# Relay.net
KiCad netlist of a schematic drawn in Altium Designer
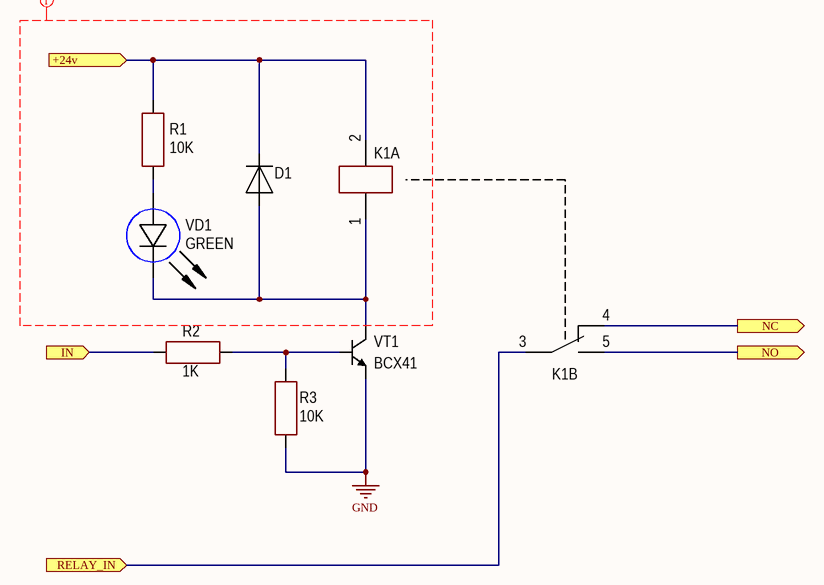
[diagram p0: Relay.SchDoc]

(export (version "E")
  (design (tool "Eeschema 10.0.6"))
  (components
    (comp (ref "D1")
      (value "~")
      (footprint "StandardCase:DIODE: SMA")
      (fields
        (field (name "MANUFACTURER") "Micro Commercial")
        (field (name "VALUEMANUFACTURERPARTNUMBER") "RS1M, SMA")
        (field (name "VOLTAGE") "1000V")
      )
      (libsource (lib "Diode") (part "Diode_single"))
    )
    (comp (ref "K1")
      (value "~")
      (footprint "PcbLib1:REL: TRJ")
      (fields
        (field (name "MANUFACTURER") "Ningbo Songle")
        (field (name "VALUEMANUFACTURERPARTNUMBER") "Electromechanics relay, 3VDC, 250VAC, 10A, 1NO, -40...+85°C")
        (field (name "PARTNUMBER") "TRJ-24VDC-SA-CD-R")
      )
      (libsource (lib "") (part "Relay_NT73_1"))
    )
    (comp (ref "R1")
      (value "10K")
      (footprint "StandardCase:RES: 1206")
      (fields
        (field (name "MANUFACTURER") "Yageo")
        (field (name "PARTNUMBER") "RC1206JR-07100RL")
        (field (name "VALUEMANUFACTURERPARTNUMBER") "Resistor film, 10K, ±5%, 1206, 0.25W, -55...+125°C")
      )
      (libsource (lib "") (part "Resistor_1206_1"))
    )
    (comp (ref "R2")
      (value "1K")
      (footprint "StandardCase:RES: 1206")
      (fields
        (field (name "MANUFACTURER") "Yageo")
        (field (name "PARTNUMBER") "RC1206JR-07100RL")
        (field (name "VALUEMANUFACTURERPARTNUMBER") "Resistor film, 1K, ±5%, 1206, 0.25W, -55...+125°C")
      )
      (libsource (lib "Resistor") (part "Resistor_1206"))
    )
    (comp (ref "R3")
      (value "10K")
      (footprint "StandardCase:RES: 1206")
      (fields
        (field (name "MANUFACTURER") "Yageo")
        (field (name "PARTNUMBER") "RC1206JR-07100RL")
        (field (name "VALUEMANUFACTURERPARTNUMBER") "Resistor film, 10K, ±5%, 1206, 0.25W, -55...+125°C")
      )
      (libsource (lib "") (part "Resistor_1206_1"))
    )
    (comp (ref "VD1")
      (value "~")
      (footprint "StandardCase:LED: 1206G")
      (fields
        (field (name "VALUEMANUFACTURERPARTNUMBER") "LED, Green, *, *, *, -55...+150°C")
        (field (name "COLOR") "GREEN")
      )
      (libsource (lib "Diode") (part "LED_single"))
    )
    (comp (ref "VT1")
      (value "~")
      (footprint "StandardCase:SOT23")
      (fields
        (field (name "MANUFACTURER") "ON Semiconductor")
        (field (name "VALUEMANUFACTURERPARTNUMBER") "NPN transistor, 45V, 100mA, 100MHz, 300mW, 0.6V, 420, SOT-23, -55...+125°C")
        (field (name "PARTNUMBER") "BCX41")
      )
      (libsource (lib "Transistor") (part "BJT_NPN_132"))
    )
  )
  (nets
    (net (code "1") (name "/+24v") (class "Default")
      (node (ref "D1") (pin "2") (pinfunction "2_2") (pintype "passive"))
      (node (ref "K1") (pin "2") (pinfunction "2_2") (pintype "passive"))
      (node (ref "R1") (pin "1") (pinfunction "1_1") (pintype "passive"))
    )
    (net (code "2") (name "/IN") (class "Default")
      (node (ref "R2") (pin "1") (pinfunction "1_1") (pintype "passive"))
    )
    (net (code "3") (name "/NC") (class "Default")
      (node (ref "K1") (pin "4") (pinfunction "4_4") (pintype "passive"))
    )
    (net (code "4") (name "/NO") (class "Default")
      (node (ref "K1") (pin "5") (pinfunction "5_5") (pintype "passive"))
    )
    (net (code "5") (name "/RELAY_IN") (class "Default")
      (node (ref "K1") (pin "3") (pinfunction "3_3") (pintype "passive"))
    )
    (net (code "6") (name "GND") (class "Default")
      (node (ref "R3") (pin "2") (pinfunction "2_2") (pintype "passive"))
      (node (ref "VT1") (pin "2") (pinfunction "E_2") (pintype "passive"))
    )
    (net (code "7") (name "Net-(VD1-A)") (class "Default")
      (node (ref "R1") (pin "2") (pinfunction "2_2") (pintype "passive"))
      (node (ref "VD1") (pin "1") (pinfunction "A_1") (pintype "passive"))
    )
    (net (code "8") (name "Net-(VD1-C)") (class "Default")
      (node (ref "D1") (pin "1") (pinfunction "1_1") (pintype "passive"))
      (node (ref "K1") (pin "1") (pinfunction "1_1") (pintype "passive"))
      (node (ref "VD1") (pin "2") (pinfunction "C_2") (pintype "passive"))
      (node (ref "VT1") (pin "3") (pinfunction "C_3") (pintype "passive"))
    )
    (net (code "9") (name "Net-(VT1-B)") (class "Default")
      (node (ref "R2") (pin "2") (pinfunction "2_2") (pintype "passive"))
      (node (ref "R3") (pin "1") (pinfunction "1_1") (pintype "passive"))
      (node (ref "VT1") (pin "1") (pinfunction "B_1") (pintype "passive"))
    )
  )
)
